# KMX62.net
KiCad netlist of a schematic drawn in Altium Designer
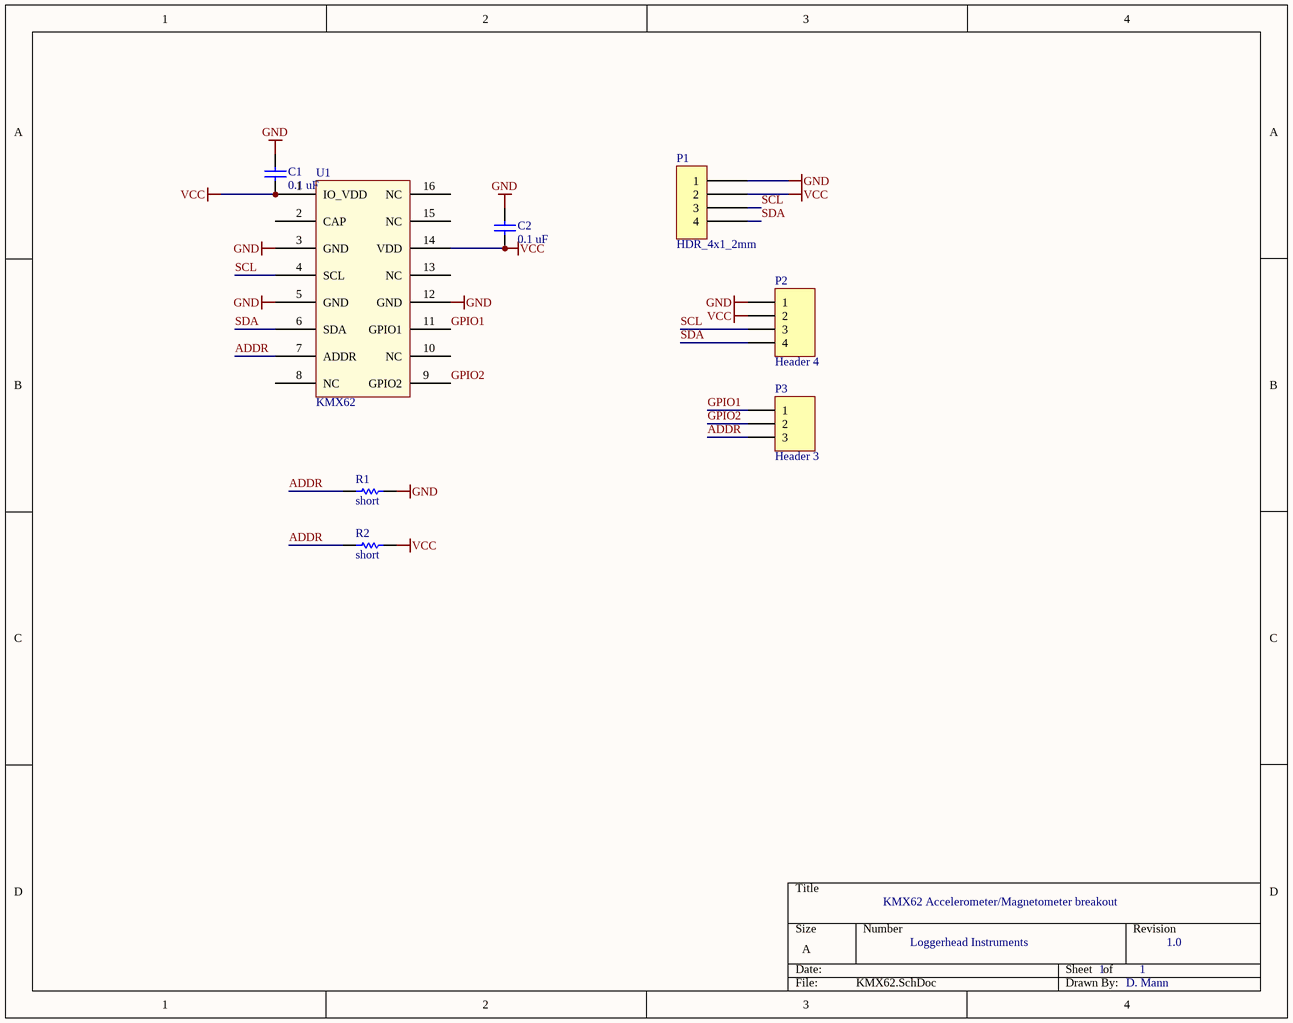
[diagram p0: KMX62.SchDoc]

(export (version "E")
  (design (tool "Eeschema 10.0.6"))
  (components
    (comp (ref "C1")
      (value "0.1 uF")
      (footprint "0402")
      (description "Ceramic Chip Capacitor - Standard")
      (fields (field (name "PUBLISHER") "Altium Limited"))
      (libsource (lib "KEMET Chip Capacitor") (part "C0402"))
    )
    (comp (ref "C2")
      (value "0.1 uF")
      (footprint "0402")
      (description "Ceramic Chip Capacitor - Standard")
      (fields (field (name "PUBLISHER") "Altium Limited"))
      (libsource (lib "KEMET Chip Capacitor") (part "C0402"))
    )
    (comp (ref "P1")
      (value "HDR_4x1_2mm")
      (footprint "Hdr_4x1_2mm")
      (libsource (lib "Loggerhead") (part "HDR_4x1_2mm"))
    )
    (comp (ref "P2")
      (value "Header 4")
      (footprint "HDR1X4")
      (description "Header, 4-Pin")
      (fields (field (name "PUBLISHER") "Altium Limited"))
      (libsource (lib "Miscellaneous Connectors") (part "Header 4"))
    )
    (comp (ref "P3")
      (value "Header 3")
      (footprint "HDR1X3")
      (description "Header, 3-Pin")
      (fields (field (name "PUBLISHER") "Altium Limited"))
      (libsource (lib "Miscellaneous Connectors") (part "Header 3"))
    )
    (comp (ref "R1")
      (value "short")
      (footprint "3-0603")
      (fields (field (name "PUBLISHER") "Altium Limited"))
      (libsource (lib "Panasonic Resistor") (part "ERJ3RK"))
    )
    (comp (ref "R2")
      (value "short")
      (footprint "3-0603")
      (fields (field (name "PUBLISHER") "Altium Limited"))
      (libsource (lib "Panasonic Resistor") (part "ERJ3RK"))
    )
    (comp (ref "U1")
      (value "KMX62")
      (footprint "Kionix_3x3_LGA16")
      (description "Kionix Accel/Mag")
      (libsource (lib "Loggerhead") (part "KMX62"))
    )
  )
  (nets
    (net (code "1") (name "/ADDR") (class "Default")
      (node (ref "P3") (pin "3") (pinfunction "3_3") (pintype "passive"))
      (node (ref "R1") (pin "2") (pinfunction "2_2") (pintype "passive"))
      (node (ref "R2") (pin "2") (pinfunction "2_2") (pintype "passive"))
      (node (ref "U1") (pin "7") (pinfunction "ADDR_7") (pintype "passive"))
    )
    (net (code "2") (name "/GPIO1") (class "Default")
      (node (ref "P3") (pin "1") (pinfunction "1_1") (pintype "passive"))
      (node (ref "U1") (pin "11") (pinfunction "GPIO1_11") (pintype "passive"))
    )
    (net (code "3") (name "/GPIO2") (class "Default")
      (node (ref "P3") (pin "2") (pinfunction "2_2") (pintype "passive"))
      (node (ref "U1") (pin "9") (pinfunction "GPIO2_9") (pintype "passive"))
    )
    (net (code "4") (name "/SCL") (class "Default")
      (node (ref "P1") (pin "3") (pinfunction "3_3") (pintype "passive"))
      (node (ref "P2") (pin "3") (pinfunction "3_3") (pintype "passive"))
      (node (ref "U1") (pin "4") (pinfunction "SCL_4") (pintype "passive"))
    )
    (net (code "5") (name "/SDA") (class "Default")
      (node (ref "P1") (pin "4") (pinfunction "4_4") (pintype "passive"))
      (node (ref "P2") (pin "4") (pinfunction "4_4") (pintype "passive"))
      (node (ref "U1") (pin "6") (pinfunction "SDA_6") (pintype "passive"))
    )
    (net (code "6") (name "GND") (class "Default")
      (node (ref "C1") (pin "1") (pinfunction "1_1") (pintype "passive"))
      (node (ref "C2") (pin "1") (pinfunction "1_1") (pintype "passive"))
      (node (ref "P1") (pin "1") (pinfunction "1_1") (pintype "passive"))
      (node (ref "P2") (pin "1") (pinfunction "1_1") (pintype "passive"))
      (node (ref "R1") (pin "1") (pinfunction "1_1") (pintype "passive"))
      (node (ref "U1") (pin "12") (pinfunction "GND_12") (pintype "passive"))
      (node (ref "U1") (pin "3") (pinfunction "GND_3") (pintype "passive"))
      (node (ref "U1") (pin "5") (pinfunction "GND_5") (pintype "passive"))
    )
    (net (code "7") (name "VCC") (class "Default")
      (node (ref "C1") (pin "2") (pinfunction "2_2") (pintype "passive"))
      (node (ref "C2") (pin "2") (pinfunction "2_2") (pintype "passive"))
      (node (ref "P1") (pin "2") (pinfunction "2_2") (pintype "passive"))
      (node (ref "P2") (pin "2") (pinfunction "2_2") (pintype "passive"))
      (node (ref "R2") (pin "1") (pinfunction "1_1") (pintype "passive"))
      (node (ref "U1") (pin "1") (pinfunction "IO_VDD_1") (pintype "passive"))
      (node (ref "U1") (pin "14") (pinfunction "VDD_14") (pintype "passive"))
    )
    (net (code "8") (name "unconnected-(U1-CAP-Pad2)") (class "Default")
      (node (ref "U1") (pin "2") (pinfunction "CAP_2") (pintype "passive"))
    )
    (net (code "9") (name "unconnected-(U1-NC-Pad8)") (class "Default")
      (node (ref "U1") (pin "8") (pinfunction "NC_8") (pintype "passive"))
    )
    (net (code "10") (name "unconnected-(U1-NC-Pad10)") (class "Default")
      (node (ref "U1") (pin "10") (pinfunction "NC_10") (pintype "passive"))
    )
    (net (code "11") (name "unconnected-(U1-NC-Pad13)") (class "Default")
      (node (ref "U1") (pin "13") (pinfunction "NC_13") (pintype "passive"))
    )
    (net (code "12") (name "unconnected-(U1-NC-Pad15)") (class "Default")
      (node (ref "U1") (pin "15") (pinfunction "NC_15") (pintype "passive"))
    )
    (net (code "13") (name "unconnected-(U1-NC-Pad16)") (class "Default")
      (node (ref "U1") (pin "16") (pinfunction "NC_16") (pintype "passive"))
    )
  )
)
